# DUAL_RPS.net
KiCad netlist of a schematic drawn in Altium Designer
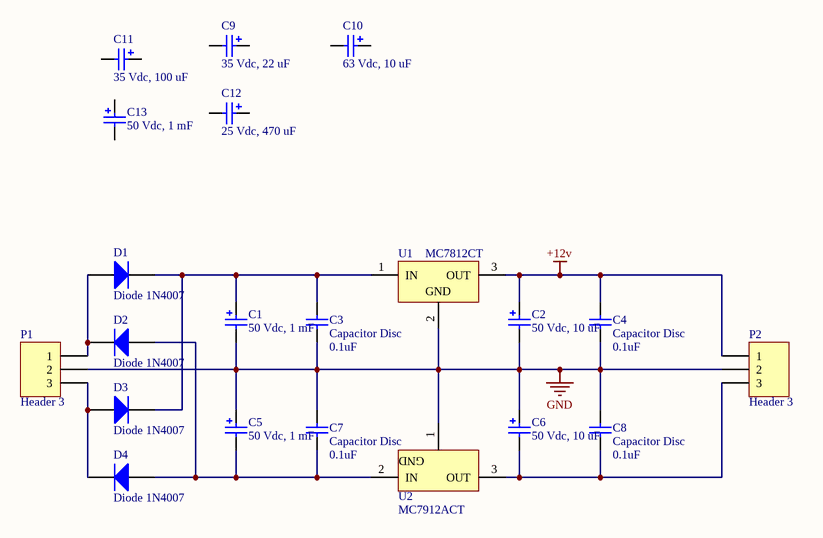
[diagram p0: DUAL_RPS.SchDoc]

(export (version "E")
  (design (tool "Eeschema 10.0.6"))
  (components
    (comp (ref "C1")
      (value "50 Vdc, 1 mF")
      (footprint "WCAP-ATG8_13x25x5")
      (description "WCAP-ATG8 Aluminum Electrolytic Capacitors, 13x25mm, 50 Vdc, 1 mF")
      (fields (field (name "PART NUMBER") "860010678024") (field (name "PUBLISHER") "Wurth Elektronik"))
      (libsource (lib "Altium_Alu_Elec_Caps_THT") (part "860010678024"))
    )
    (comp (ref "C2")
      (value "50 Vdc, 10 uF")
      (footprint "WCAP-ATG8_5x11x2")
      (description "WCAP-ATG8 Aluminum Electrolytic Capacitors, 5x11mm, 50 Vdc, 10 uF")
      (fields (field (name "PART NUMBER") "860010672009") (field (name "PUBLISHER") "Wurth Elektronik"))
      (libsource (lib "Altium_Alu_Elec_Caps_THT") (part "860010672009"))
    )
    (comp (ref "C3")
      (value "Capacitor Disc")
      (footprint "RAD-0.3")
      (description "Capacitor")
      (fields (field (name "ALTIUM_VALUE") "0.1uF") (field (name "PUBLISHER") "Altium Limited"))
      (libsource (lib "Miscellaneous Devices") (part "Cap"))
    )
    (comp (ref "C4")
      (value "Capacitor Disc")
      (footprint "RAD-0.3")
      (description "Capacitor")
      (fields (field (name "ALTIUM_VALUE") "0.1uF") (field (name "PUBLISHER") "Altium Limited"))
      (libsource (lib "Miscellaneous Devices") (part "Cap"))
    )
    (comp (ref "C5")
      (value "50 Vdc, 1 mF")
      (footprint "WCAP-ATG8_13x25x5")
      (description "WCAP-ATG8 Aluminum Electrolytic Capacitors, 13x25mm, 50 Vdc, 1 mF")
      (fields (field (name "PART NUMBER") "860010678024") (field (name "PUBLISHER") "Wurth Elektronik"))
      (libsource (lib "Altium_Alu_Elec_Caps_THT") (part "860010678024"))
    )
    (comp (ref "C6")
      (value "50 Vdc, 10 uF")
      (footprint "WCAP-ATG8_5x11x2")
      (description "WCAP-ATG8 Aluminum Electrolytic Capacitors, 5x11mm, 50 Vdc, 10 uF")
      (fields (field (name "PART NUMBER") "860010672009") (field (name "PUBLISHER") "Wurth Elektronik"))
      (libsource (lib "Altium_Alu_Elec_Caps_THT") (part "860010672009"))
    )
    (comp (ref "C7")
      (value "Capacitor Disc")
      (footprint "RAD-0.3")
      (description "Capacitor")
      (fields (field (name "ALTIUM_VALUE") "0.1uF") (field (name "PUBLISHER") "Altium Limited"))
      (libsource (lib "Miscellaneous Devices") (part "Cap"))
    )
    (comp (ref "C8")
      (value "Capacitor Disc")
      (footprint "RAD-0.3")
      (description "Capacitor")
      (fields (field (name "ALTIUM_VALUE") "0.1uF") (field (name "PUBLISHER") "Altium Limited"))
      (libsource (lib "Miscellaneous Devices") (part "Cap"))
    )
    (comp (ref "C9")
      (value "35 Vdc, 22 uF")
      (footprint "WCAP-ATG8_5x11x2")
      (description "WCAP-ATG8 Aluminum Electrolytic Capacitors, 5x11mm, 35 Vdc, 22 uF")
      (fields (field (name "PART NUMBER") "860010572003") (field (name "PUBLISHER") "Wurth Elektronik"))
      (libsource (lib "Altium_Alu_Elec_Caps_THT") (part "860010572003"))
    )
    (comp (ref "C10")
      (value "63 Vdc, 10 uF")
      (footprint "WCAP-ATG8_5x11x2")
      (description "WCAP-ATG8 Aluminum Electrolytic Capacitors, 5x11mm, 63 Vdc, 10 uF")
      (fields (field (name "PART NUMBER") "860010772009") (field (name "PUBLISHER") "Wurth Elektronik"))
      (libsource (lib "Altium_Alu_Elec_Caps_THT") (part "860010772009"))
    )
    (comp (ref "C11")
      (value "35 Vdc, 100 uF")
      (footprint "WCAP-ATG8_6.3x11x2.5")
      (description "WCAP-ATG8 Aluminum Electrolytic Capacitors, 6.3x11mm, 35 Vdc, 100 uF")
      (fields (field (name "PART NUMBER") "860010573007") (field (name "PUBLISHER") "Wurth Elektronik"))
      (libsource (lib "Altium_Alu_Elec_Caps_THT") (part "860010573007"))
    )
    (comp (ref "C12")
      (value "25 Vdc, 470 uF")
      (footprint "WCAP-ATG8_8x11.5x3.5")
      (description "WCAP-ATG8 Aluminum Electrolytic Capacitors, 8x11.5mm, 25 Vdc, 470 uF")
      (fields (field (name "PART NUMBER") "860010474013") (field (name "PUBLISHER") "Wurth Elektronik"))
      (libsource (lib "Altium_Alu_Elec_Caps_THT") (part "860010474013"))
    )
    (comp (ref "C13")
      (value "50 Vdc, 1 mF")
      (footprint "WCAP-ATG8_13x25x5")
      (description "WCAP-ATG8 Aluminum Electrolytic Capacitors, 13x25mm, 50 Vdc, 1 mF")
      (fields (field (name "PART NUMBER") "860010678024") (field (name "PUBLISHER") "Wurth Elektronik"))
      (libsource (lib "Altium_Alu_Elec_Caps_THT") (part "860010678024"))
    )
    (comp (ref "D1")
      (value "Diode 1N4007")
      (footprint "DIO10.46-5.3x2.8")
      (description "1 Amp General Purpose Rectifier")
      (fields (field (name "PUBLISHER") "Altium Limited"))
      (libsource (lib "Miscellaneous Devices") (part "Diode 1N4007"))
    )
    (comp (ref "D2")
      (value "Diode 1N4007")
      (footprint "DIO10.46-5.3x2.8")
      (description "1 Amp General Purpose Rectifier")
      (fields (field (name "PUBLISHER") "Altium Limited"))
      (libsource (lib "Miscellaneous Devices") (part "Diode 1N4007"))
    )
    (comp (ref "D3")
      (value "Diode 1N4007")
      (footprint "DIO10.46-5.3x2.8")
      (description "1 Amp General Purpose Rectifier")
      (fields (field (name "PUBLISHER") "Altium Limited"))
      (libsource (lib "Miscellaneous Devices") (part "Diode 1N4007"))
    )
    (comp (ref "D4")
      (value "Diode 1N4007")
      (footprint "DIO10.46-5.3x2.8")
      (description "1 Amp General Purpose Rectifier")
      (fields (field (name "PUBLISHER") "Altium Limited"))
      (libsource (lib "Miscellaneous Devices") (part "Diode 1N4007"))
    )
    (comp (ref "P1")
      (value "Header 3")
      (footprint "HDR1X3")
      (description "Header, 3-Pin")
      (fields (field (name "PUBLISHER") "Altium Limited"))
      (libsource (lib "") (part "Header 3_1"))
    )
    (comp (ref "P2")
      (value "Header 3")
      (footprint "HDR1X3")
      (description "Header, 3-Pin")
      (fields (field (name "PUBLISHER") "Altium Limited"))
      (libsource (lib "Miscellaneous Connectors") (part "Header 3"))
    )
    (comp (ref "U1")
      (value "MC7812CT")
      (footprint "221A-04")
      (description "3-Terminal Positive Fixed Voltage Regulator")
      (fields (field (name "PUBLISHER") "Altium Limited"))
      (libsource (lib "Motorola Power Mgt Voltage Regulator") (part "MC7812CT"))
    )
    (comp (ref "U2")
      (value "MC7912ACT")
      (footprint "221A-04")
      (description "Three-Terminal Negative Fixed Voltage Regulator")
      (fields (field (name "PUBLISHER") "Altium Limited"))
      (libsource (lib "Motorola Power Mgt Voltage Regulator") (part "MC7912ACT"))
    )
  )
  (nets
    (net (code "1") (name "+12v") (class "Default")
      (node (ref "C2") (pin "1") (pinfunction "P_1") (pintype "passive"))
      (node (ref "C4") (pin "2") (pinfunction "2_2") (pintype "passive"))
      (node (ref "P2") (pin "1") (pinfunction "1_1") (pintype "passive"))
      (node (ref "U1") (pin "3") (pinfunction "OUT_3") (pintype "power_in"))
    )
    (net (code "2") (name "GND") (class "Default")
      (node (ref "C1") (pin "2") (pinfunction "N_2") (pintype "passive"))
      (node (ref "C2") (pin "2") (pinfunction "N_2") (pintype "passive"))
      (node (ref "C3") (pin "1") (pinfunction "1_1") (pintype "passive"))
      (node (ref "C4") (pin "1") (pinfunction "1_1") (pintype "passive"))
      (node (ref "C5") (pin "1") (pinfunction "P_1") (pintype "passive"))
      (node (ref "C6") (pin "1") (pinfunction "P_1") (pintype "passive"))
      (node (ref "C7") (pin "2") (pinfunction "2_2") (pintype "passive"))
      (node (ref "C8") (pin "2") (pinfunction "2_2") (pintype "passive"))
      (node (ref "P1") (pin "2") (pinfunction "2_2") (pintype "passive"))
      (node (ref "P2") (pin "2") (pinfunction "2_2") (pintype "passive"))
      (node (ref "U1") (pin "2") (pinfunction "GND_2") (pintype "power_in"))
      (node (ref "U2") (pin "1") (pinfunction "GND_1") (pintype "power_in"))
    )
    (net (code "3") (name "Net-(C1-P)") (class "Default")
      (node (ref "C1") (pin "1") (pinfunction "P_1") (pintype "passive"))
      (node (ref "C3") (pin "2") (pinfunction "2_2") (pintype "passive"))
      (node (ref "D1") (pin "2") (pinfunction "K_2") (pintype "passive"))
      (node (ref "D3") (pin "2") (pinfunction "K_2") (pintype "passive"))
      (node (ref "U1") (pin "1") (pinfunction "IN_1") (pintype "power_in"))
    )
    (net (code "4") (name "Net-(C5-N)") (class "Default")
      (node (ref "C5") (pin "2") (pinfunction "N_2") (pintype "passive"))
      (node (ref "C7") (pin "1") (pinfunction "1_1") (pintype "passive"))
      (node (ref "D2") (pin "1") (pinfunction "A_1") (pintype "passive"))
      (node (ref "D4") (pin "1") (pinfunction "A_1") (pintype "passive"))
      (node (ref "U2") (pin "2") (pinfunction "IN_2") (pintype "power_in"))
    )
    (net (code "5") (name "Net-(C6-N)") (class "Default")
      (node (ref "C6") (pin "2") (pinfunction "N_2") (pintype "passive"))
      (node (ref "C8") (pin "1") (pinfunction "1_1") (pintype "passive"))
      (node (ref "P2") (pin "3") (pinfunction "3_3") (pintype "passive"))
      (node (ref "U2") (pin "3") (pinfunction "OUT_3") (pintype "power_in"))
    )
    (net (code "6") (name "Net-(D1-A)") (class "Default")
      (node (ref "D1") (pin "1") (pinfunction "A_1") (pintype "passive"))
      (node (ref "D2") (pin "2") (pinfunction "K_2") (pintype "passive"))
      (node (ref "P1") (pin "1") (pinfunction "1_1") (pintype "passive"))
    )
    (net (code "7") (name "Net-(D3-A)") (class "Default")
      (node (ref "D3") (pin "1") (pinfunction "A_1") (pintype "passive"))
      (node (ref "D4") (pin "2") (pinfunction "K_2") (pintype "passive"))
      (node (ref "P1") (pin "3") (pinfunction "3_3") (pintype "passive"))
    )
    (net (code "8") (name "unconnected-(C9-N-Pad2)") (class "Default")
      (node (ref "C9") (pin "2") (pinfunction "N_2") (pintype "passive"))
    )
    (net (code "9") (name "unconnected-(C9-P-Pad1)") (class "Default")
      (node (ref "C9") (pin "1") (pinfunction "P_1") (pintype "passive"))
    )
    (net (code "10") (name "unconnected-(C10-N-Pad2)") (class "Default")
      (node (ref "C10") (pin "2") (pinfunction "N_2") (pintype "passive"))
    )
    (net (code "11") (name "unconnected-(C10-P-Pad1)") (class "Default")
      (node (ref "C10") (pin "1") (pinfunction "P_1") (pintype "passive"))
    )
    (net (code "12") (name "unconnected-(C11-N-Pad2)") (class "Default")
      (node (ref "C11") (pin "2") (pinfunction "N_2") (pintype "passive"))
    )
    (net (code "13") (name "unconnected-(C11-P-Pad1)") (class "Default")
      (node (ref "C11") (pin "1") (pinfunction "P_1") (pintype "passive"))
    )
    (net (code "14") (name "unconnected-(C12-N-Pad2)") (class "Default")
      (node (ref "C12") (pin "2") (pinfunction "N_2") (pintype "passive"))
    )
    (net (code "15") (name "unconnected-(C12-P-Pad1)") (class "Default")
      (node (ref "C12") (pin "1") (pinfunction "P_1") (pintype "passive"))
    )
    (net (code "16") (name "unconnected-(C13-N-Pad2)") (class "Default")
      (node (ref "C13") (pin "2") (pinfunction "N_2") (pintype "passive"))
    )
    (net (code "17") (name "unconnected-(C13-P-Pad1)") (class "Default")
      (node (ref "C13") (pin "1") (pinfunction "P_1") (pintype "passive"))
    )
  )
)
